# chainclock.net
KiCad netlist of a schematic drawn in EAGLE
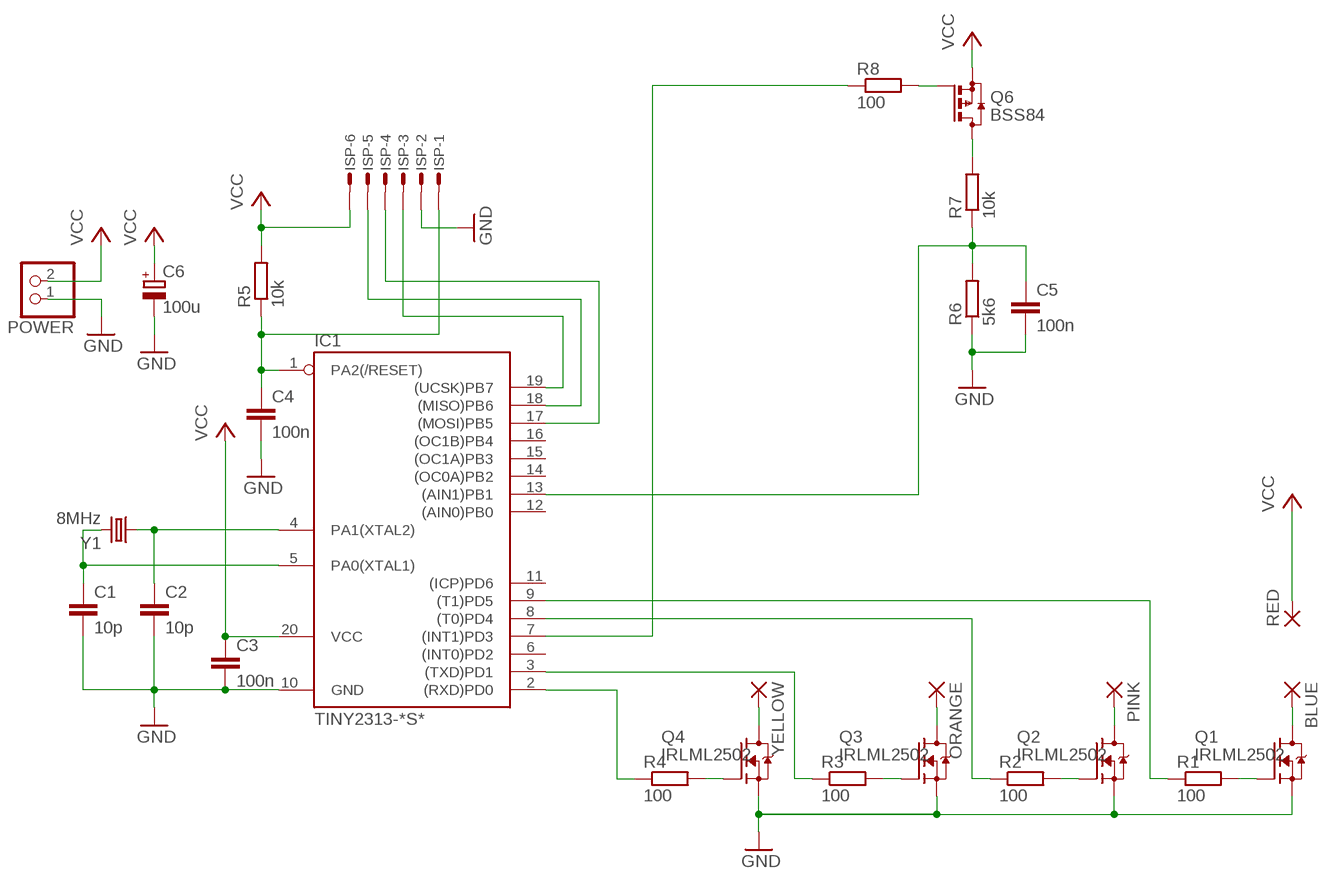
[diagram p0: schematic, sheet 1]

(export (version "E")
  (design (tool "Eeschema 10.0.6"))
  (components
    (comp (ref "BLUE")
      (value "SMD2")
      (footprint "eagle-import:SMD1,27-2,54")
      (libsource (lib "eagle-import") (part "SMD2"))
    )
    (comp (ref "C1")
      (value "10p")
      (footprint "eagle-import:C0603")
      (libsource (lib "eagle-import") (part "C-EUC0603"))
    )
    (comp (ref "C2")
      (value "10p")
      (footprint "eagle-import:C0603")
      (libsource (lib "eagle-import") (part "C-EUC0603"))
    )
    (comp (ref "C3")
      (value "100n")
      (footprint "eagle-import:C0603")
      (libsource (lib "eagle-import") (part "C-EUC0603"))
    )
    (comp (ref "C4")
      (value "100n")
      (footprint "eagle-import:C0603")
      (libsource (lib "eagle-import") (part "C-EUC0603"))
    )
    (comp (ref "C5")
      (value "100n")
      (footprint "eagle-import:C0603")
      (libsource (lib "eagle-import") (part "C-EUC0603"))
    )
    (comp (ref "C6")
      (value "100u")
      (footprint "eagle-import:E2,5-6")
      (libsource (lib "eagle-import") (part "CPOL-EUE2.5-6"))
    )
    (comp (ref "IC1")
      (value "TINY2313-*S*")
      (footprint "eagle-import:SO20L$")
      (libsource (lib "eagle-import") (part "TINY2313-S"))
    )
    (comp (ref "ISP")
      (value "MICROMATCH-6SMF")
      (footprint "eagle-import:MMT-F-SMD-6")
      (libsource (lib "eagle-import") (part "MICROMATCH-6SMF"))
    )
    (comp (ref "ORANGE")
      (value "SMD2")
      (footprint "eagle-import:SMD1,27-2,54")
      (libsource (lib "eagle-import") (part "SMD2"))
    )
    (comp (ref "PINK")
      (value "SMD2")
      (footprint "eagle-import:SMD1,27-2,54")
      (libsource (lib "eagle-import") (part "SMD2"))
    )
    (comp (ref "POWER")
      (value "PINHD-1X2/90")
      (footprint "eagle-import:1X02_90")
      (libsource (lib "eagle-import") (part "PINHD-1X2/90"))
    )
    (comp (ref "Q1")
      (value "IRLML2502")
      (footprint "eagle-import:SOT23-3")
      (libsource (lib "eagle-import") (part "IRLML2502"))
    )
    (comp (ref "Q2")
      (value "IRLML2502")
      (footprint "eagle-import:SOT23-3")
      (libsource (lib "eagle-import") (part "IRLML2502"))
    )
    (comp (ref "Q3")
      (value "IRLML2502")
      (footprint "eagle-import:SOT23-3")
      (libsource (lib "eagle-import") (part "IRLML2502"))
    )
    (comp (ref "Q4")
      (value "IRLML2502")
      (footprint "eagle-import:SOT23-3")
      (libsource (lib "eagle-import") (part "IRLML2502"))
    )
    (comp (ref "Q6")
      (value "BSS84")
      (footprint "eagle-import:SOT23")
      (libsource (lib "eagle-import") (part "BSS84"))
    )
    (comp (ref "R1")
      (value "100")
      (footprint "eagle-import:R0603")
      (libsource (lib "eagle-import") (part "R-EU_R0603"))
    )
    (comp (ref "R2")
      (value "100")
      (footprint "eagle-import:R0603")
      (libsource (lib "eagle-import") (part "R-EU_R0603"))
    )
    (comp (ref "R3")
      (value "100")
      (footprint "eagle-import:R0603")
      (libsource (lib "eagle-import") (part "R-EU_R0603"))
    )
    (comp (ref "R4")
      (value "100")
      (footprint "eagle-import:R0603")
      (libsource (lib "eagle-import") (part "R-EU_R0603"))
    )
    (comp (ref "R5")
      (value "10k")
      (footprint "eagle-import:R0603")
      (libsource (lib "eagle-import") (part "R-EU_R0603"))
    )
    (comp (ref "R6")
      (value "5k6")
      (footprint "eagle-import:R0603")
      (libsource (lib "eagle-import") (part "R-EU_R0603"))
    )
    (comp (ref "R7")
      (value "10k")
      (footprint "eagle-import:R0603")
      (libsource (lib "eagle-import") (part "R-EU_R0603"))
    )
    (comp (ref "R8")
      (value "100")
      (footprint "eagle-import:R0603")
      (libsource (lib "eagle-import") (part "R-EU_R0603"))
    )
    (comp (ref "RED")
      (value "SMD2")
      (footprint "eagle-import:SMD1,27-2,54")
      (libsource (lib "eagle-import") (part "SMD2"))
    )
    (comp (ref "Y1")
      (value "8MHz")
      (footprint "eagle-import:HC49UP")
      (libsource (lib "eagle-import") (part "CRYSTALHC49UP"))
    )
    (comp (ref "YELLOW")
      (value "SMD2")
      (footprint "eagle-import:SMD1,27-2,54")
      (libsource (lib "eagle-import") (part "SMD2"))
    )
  )
  (nets
    (net (code "1") (name "GND") (class "Default")
      (node (ref "C1") (pin "2") (pinfunction "2_2") (pintype "passive"))
      (node (ref "C2") (pin "2") (pinfunction "2_2") (pintype "passive"))
      (node (ref "C3") (pin "2") (pinfunction "2_2") (pintype "passive"))
      (node (ref "C4") (pin "2") (pinfunction "2_2") (pintype "passive"))
      (node (ref "C5") (pin "2") (pinfunction "2_2") (pintype "passive"))
      (node (ref "C6") (pin "-") (pinfunction "-_-") (pintype "passive"))
      (node (ref "IC1") (pin "10") (pinfunction "GND_10") (pintype "power_in"))
      (node (ref "ISP") (pin "2") (pinfunction "S_2") (pintype "passive"))
      (node (ref "POWER") (pin "1") (pinfunction "1_1") (pintype "passive"))
      (node (ref "Q1") (pin "2") (pinfunction "S_2") (pintype "passive"))
      (node (ref "Q2") (pin "2") (pinfunction "S_2") (pintype "passive"))
      (node (ref "Q3") (pin "2") (pinfunction "S_2") (pintype "passive"))
      (node (ref "Q4") (pin "2") (pinfunction "S_2") (pintype "passive"))
      (node (ref "R6") (pin "1") (pinfunction "1_1") (pintype "passive"))
    )
    (net (code "2") (name "Net-(BLUE-P)") (class "Default")
      (node (ref "BLUE") (pin "1") (pinfunction "P_1") (pintype "passive"))
      (node (ref "Q1") (pin "3") (pinfunction "D_3") (pintype "passive"))
    )
    (net (code "3") (name "Net-(IC1-(AIN1)PB1)") (class "Default")
      (node (ref "C5") (pin "1") (pinfunction "1_1") (pintype "passive"))
      (node (ref "IC1") (pin "13") (pinfunction "(AIN1)PB1_13") (pintype "bidirectional"))
      (node (ref "R6") (pin "2") (pinfunction "2_2") (pintype "passive"))
      (node (ref "R7") (pin "1") (pinfunction "1_1") (pintype "passive"))
    )
    (net (code "4") (name "Net-(IC1-(INT1)PD3)") (class "Default")
      (node (ref "IC1") (pin "7") (pinfunction "(INT1)PD3_7") (pintype "bidirectional"))
      (node (ref "R8") (pin "1") (pinfunction "1_1") (pintype "passive"))
    )
    (net (code "5") (name "Net-(IC1-(MISO)PB6)") (class "Default")
      (node (ref "IC1") (pin "18") (pinfunction "(MISO)PB6_18") (pintype "bidirectional"))
      (node (ref "ISP") (pin "5") (pinfunction "S_5") (pintype "passive"))
    )
    (net (code "6") (name "Net-(IC1-(MOSI)PB5)") (class "Default")
      (node (ref "IC1") (pin "17") (pinfunction "(MOSI)PB5_17") (pintype "bidirectional"))
      (node (ref "ISP") (pin "4") (pinfunction "S_4") (pintype "passive"))
    )
    (net (code "7") (name "Net-(IC1-(RXD)PD0)") (class "Default")
      (node (ref "IC1") (pin "2") (pinfunction "(RXD)PD0_2") (pintype "bidirectional"))
      (node (ref "R4") (pin "1") (pinfunction "1_1") (pintype "passive"))
    )
    (net (code "8") (name "Net-(IC1-(T0)PD4)") (class "Default")
      (node (ref "IC1") (pin "8") (pinfunction "(T0)PD4_8") (pintype "bidirectional"))
      (node (ref "R2") (pin "1") (pinfunction "1_1") (pintype "passive"))
    )
    (net (code "9") (name "Net-(IC1-(T1)PD5)") (class "Default")
      (node (ref "IC1") (pin "9") (pinfunction "(T1)PD5_9") (pintype "bidirectional"))
      (node (ref "R1") (pin "1") (pinfunction "1_1") (pintype "passive"))
    )
    (net (code "10") (name "Net-(IC1-(TXD)PD1)") (class "Default")
      (node (ref "IC1") (pin "3") (pinfunction "(TXD)PD1_3") (pintype "bidirectional"))
      (node (ref "R3") (pin "1") (pinfunction "1_1") (pintype "passive"))
    )
    (net (code "11") (name "Net-(IC1-(UCSK)PB7)") (class "Default")
      (node (ref "IC1") (pin "19") (pinfunction "(UCSK)PB7_19") (pintype "bidirectional"))
      (node (ref "ISP") (pin "3") (pinfunction "S_3") (pintype "passive"))
    )
    (net (code "12") (name "Net-(IC1-PA0(XTAL1))") (class "Default")
      (node (ref "C1") (pin "1") (pinfunction "1_1") (pintype "passive"))
      (node (ref "IC1") (pin "5") (pinfunction "PA0(XTAL1)_5") (pintype "bidirectional"))
      (node (ref "Y1") (pin "2") (pinfunction "2_2") (pintype "passive"))
    )
    (net (code "13") (name "Net-(IC1-PA1(XTAL2))") (class "Default")
      (node (ref "C2") (pin "1") (pinfunction "1_1") (pintype "passive"))
      (node (ref "IC1") (pin "4") (pinfunction "PA1(XTAL2)_4") (pintype "bidirectional"))
      (node (ref "Y1") (pin "1") (pinfunction "1_1") (pintype "passive"))
    )
    (net (code "14") (name "Net-(IC1-PA2({slash}RESET))") (class "Default")
      (node (ref "C4") (pin "1") (pinfunction "1_1") (pintype "passive"))
      (node (ref "IC1") (pin "1") (pinfunction "PA2(/RESET)_1") (pintype "input"))
      (node (ref "ISP") (pin "1") (pinfunction "S_1") (pintype "passive"))
      (node (ref "R5") (pin "1") (pinfunction "1_1") (pintype "passive"))
    )
    (net (code "15") (name "Net-(ORANGE-P)") (class "Default")
      (node (ref "ORANGE") (pin "1") (pinfunction "P_1") (pintype "passive"))
      (node (ref "Q3") (pin "3") (pinfunction "D_3") (pintype "passive"))
    )
    (net (code "16") (name "Net-(PINK-P)") (class "Default")
      (node (ref "PINK") (pin "1") (pinfunction "P_1") (pintype "passive"))
      (node (ref "Q2") (pin "3") (pinfunction "D_3") (pintype "passive"))
    )
    (net (code "17") (name "Net-(Q1-G)") (class "Default")
      (node (ref "Q1") (pin "1") (pinfunction "G_1") (pintype "passive"))
      (node (ref "R1") (pin "2") (pinfunction "2_2") (pintype "passive"))
    )
    (net (code "18") (name "Net-(Q2-G)") (class "Default")
      (node (ref "Q2") (pin "1") (pinfunction "G_1") (pintype "passive"))
      (node (ref "R2") (pin "2") (pinfunction "2_2") (pintype "passive"))
    )
    (net (code "19") (name "Net-(Q3-G)") (class "Default")
      (node (ref "Q3") (pin "1") (pinfunction "G_1") (pintype "passive"))
      (node (ref "R3") (pin "2") (pinfunction "2_2") (pintype "passive"))
    )
    (net (code "20") (name "Net-(Q4-D)") (class "Default")
      (node (ref "Q4") (pin "3") (pinfunction "D_3") (pintype "passive"))
      (node (ref "YELLOW") (pin "1") (pinfunction "P_1") (pintype "passive"))
    )
    (net (code "21") (name "Net-(Q4-G)") (class "Default")
      (node (ref "Q4") (pin "1") (pinfunction "G_1") (pintype "passive"))
      (node (ref "R4") (pin "2") (pinfunction "2_2") (pintype "passive"))
    )
    (net (code "22") (name "Net-(Q6-D)") (class "Default")
      (node (ref "Q6") (pin "3") (pinfunction "D_3") (pintype "passive"))
      (node (ref "R7") (pin "2") (pinfunction "2_2") (pintype "passive"))
    )
    (net (code "23") (name "Net-(Q6-G)") (class "Default")
      (node (ref "Q6") (pin "1") (pinfunction "G_1") (pintype "passive"))
      (node (ref "R8") (pin "2") (pinfunction "2_2") (pintype "passive"))
    )
    (net (code "24") (name "VCC") (class "Default")
      (node (ref "C3") (pin "1") (pinfunction "1_1") (pintype "passive"))
      (node (ref "C6") (pin "+") (pinfunction "+_+") (pintype "passive"))
      (node (ref "IC1") (pin "20") (pinfunction "VCC_20") (pintype "power_in"))
      (node (ref "ISP") (pin "6") (pinfunction "S_6") (pintype "passive"))
      (node (ref "POWER") (pin "2") (pinfunction "2_2") (pintype "passive"))
      (node (ref "Q6") (pin "2") (pinfunction "S_2") (pintype "passive"))
      (node (ref "R5") (pin "2") (pinfunction "2_2") (pintype "passive"))
      (node (ref "RED") (pin "1") (pinfunction "P_1") (pintype "passive"))
    )
    (net (code "25") (name "unconnected-(IC1-(AIN0)PB0-Pad12)") (class "Default")
      (node (ref "IC1") (pin "12") (pinfunction "(AIN0)PB0_12") (pintype "bidirectional"))
    )
    (net (code "26") (name "unconnected-(IC1-(ICP)PD6-Pad11)") (class "Default")
      (node (ref "IC1") (pin "11") (pinfunction "(ICP)PD6_11") (pintype "bidirectional"))
    )
    (net (code "27") (name "unconnected-(IC1-(INT0)PD2-Pad6)") (class "Default")
      (node (ref "IC1") (pin "6") (pinfunction "(INT0)PD2_6") (pintype "bidirectional"))
    )
    (net (code "28") (name "unconnected-(IC1-(OC0A)PB2-Pad14)") (class "Default")
      (node (ref "IC1") (pin "14") (pinfunction "(OC0A)PB2_14") (pintype "bidirectional"))
    )
    (net (code "29") (name "unconnected-(IC1-(OC1A)PB3-Pad15)") (class "Default")
      (node (ref "IC1") (pin "15") (pinfunction "(OC1A)PB3_15") (pintype "bidirectional"))
    )
    (net (code "30") (name "unconnected-(IC1-(OC1B)PB4-Pad16)") (class "Default")
      (node (ref "IC1") (pin "16") (pinfunction "(OC1B)PB4_16") (pintype "bidirectional"))
    )
  )
)
